# LDO.net
KiCad netlist of a schematic drawn in EAGLE
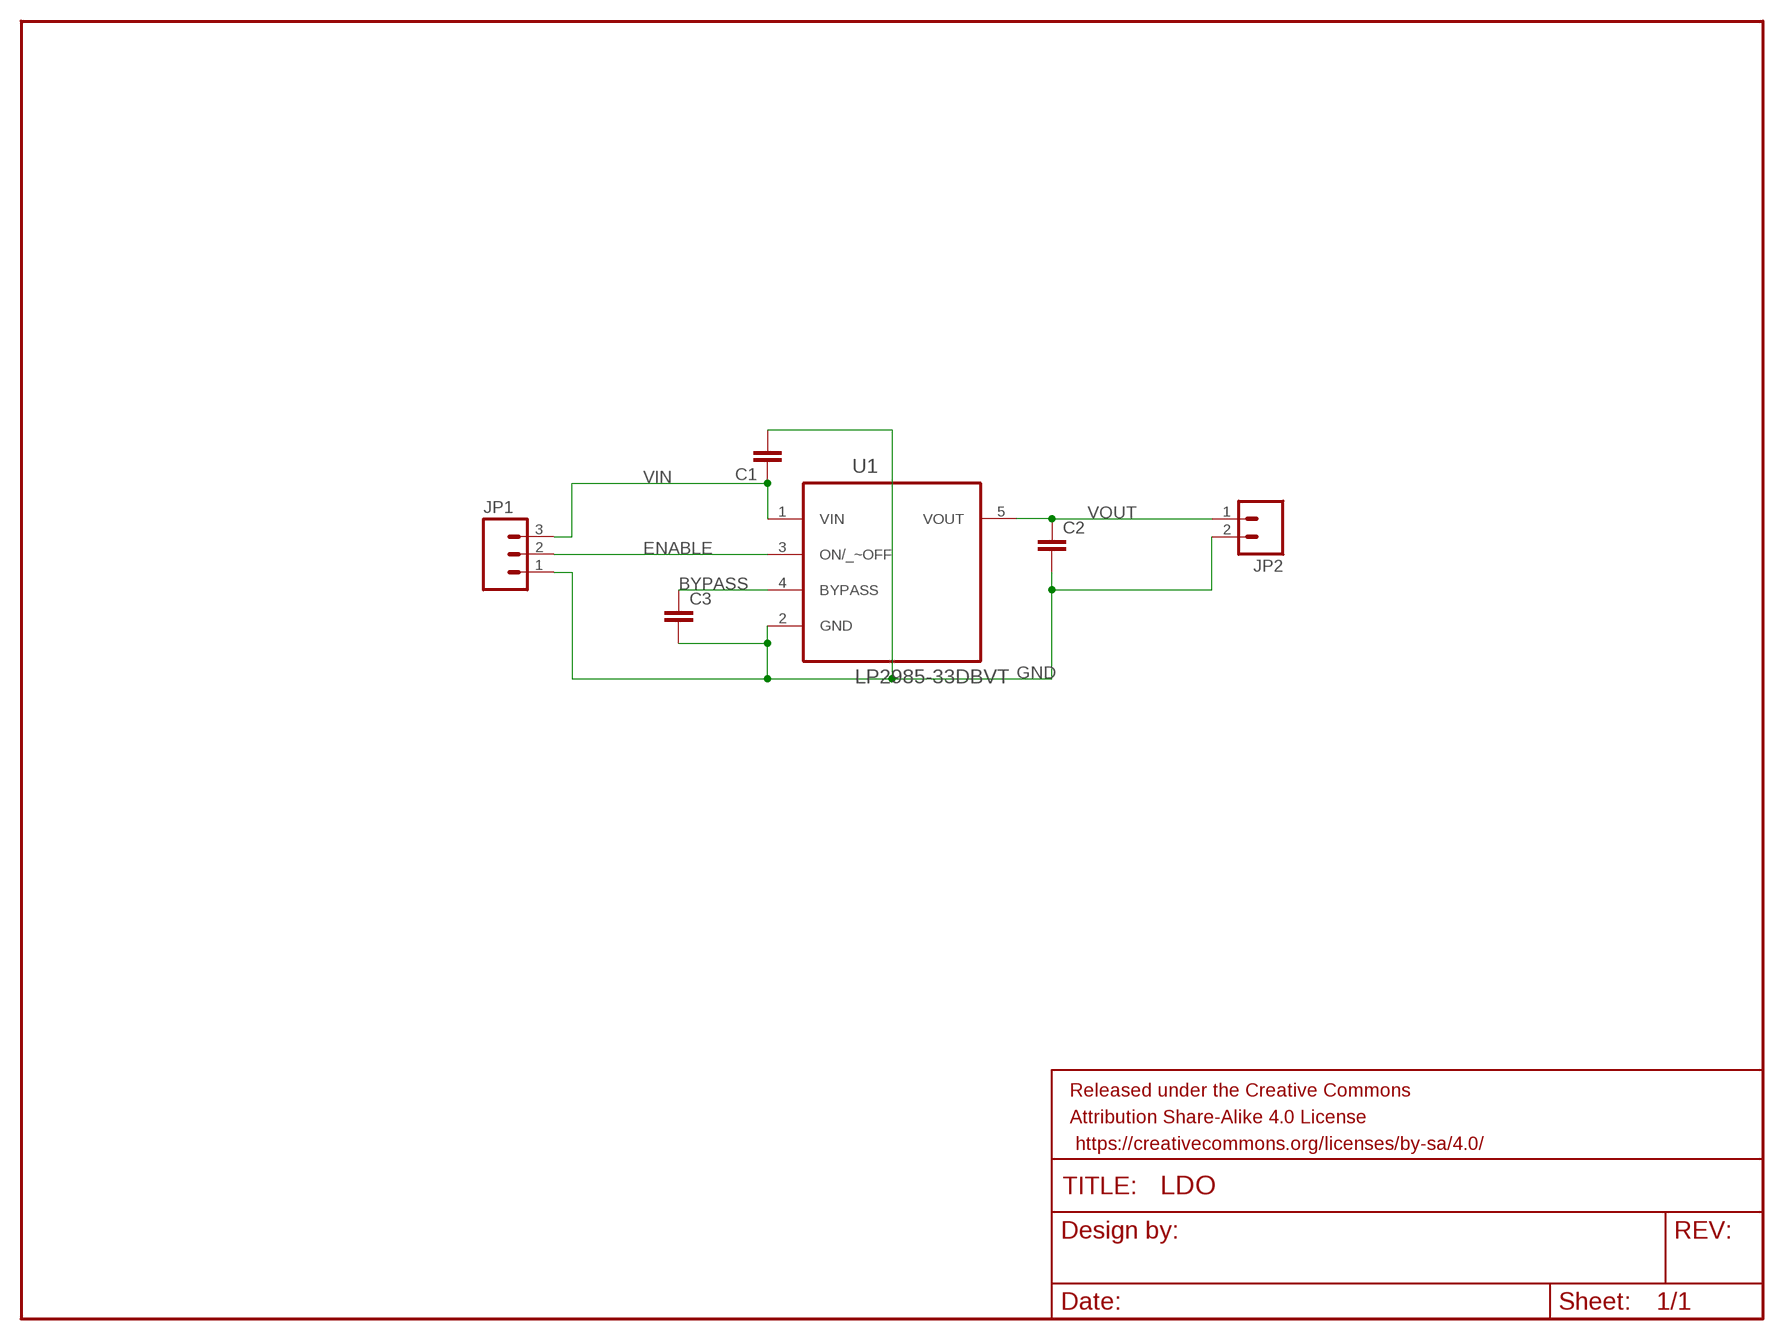
[diagram p0: schematic, sheet 1]

(export (version "E")
  (design (tool "Eeschema 10.0.6"))
  (components
    (comp (ref "C1")
      (value "CAP0603-CAP")
      (footprint "eagle-import:0603-CAP")
      (libsource (lib "eagle-import") (part "CAP0603-CAP"))
    )
    (comp (ref "C2")
      (value "CAP0603-CAP")
      (footprint "eagle-import:0603-CAP")
      (libsource (lib "eagle-import") (part "CAP0603-CAP"))
    )
    (comp (ref "C3")
      (value "CAP0603-CAP")
      (footprint "eagle-import:0603-CAP")
      (libsource (lib "eagle-import") (part "CAP0603-CAP"))
    )
    (comp (ref "FRAME1")
      (value "FRAME-LETTER")
      (footprint "eagle-import:CREATIVE_COMMONS")
      (libsource (lib "eagle-import") (part "FRAME-LETTER"))
    )
    (comp (ref "JP1")
      (value "M03PTH")
      (footprint "eagle-import:1X03")
      (libsource (lib "eagle-import") (part "M03PTH"))
    )
    (comp (ref "JP2")
      (value "M02PTH")
      (footprint "eagle-import:1X02")
      (libsource (lib "eagle-import") (part "M02PTH"))
    )
    (comp (ref "U1")
      (value "LP2985-33DBVT")
      (footprint "eagle-import:SOT95P280X145-5N")
      (fields (field (name "MF") "Texas Instruments"))
      (libsource (lib "eagle-import") (part "LP2985-33DBVT"))
    )
  )
  (nets
    (net (code "1") (name "/BYPASS") (class "Default")
      (node (ref "C3") (pin "1") (pinfunction "1_1") (pintype "passive"))
      (node (ref "U1") (pin "4") (pinfunction "BYPASS_4") (pintype "input"))
    )
    (net (code "2") (name "/ENABLE") (class "Default")
      (node (ref "JP1") (pin "2") (pinfunction "2_2") (pintype "passive"))
      (node (ref "U1") (pin "3") (pinfunction "ON/_~{OFF}_3") (pintype "input"))
    )
    (net (code "3") (name "/GND") (class "Default")
      (node (ref "C1") (pin "2") (pinfunction "2_2") (pintype "passive"))
      (node (ref "C2") (pin "2") (pinfunction "2_2") (pintype "passive"))
      (node (ref "C3") (pin "2") (pinfunction "2_2") (pintype "passive"))
      (node (ref "JP1") (pin "1") (pinfunction "1_1") (pintype "passive"))
      (node (ref "JP2") (pin "2") (pinfunction "2_2") (pintype "passive"))
      (node (ref "U1") (pin "2") (pinfunction "GND_2") (pintype "passive"))
    )
    (net (code "4") (name "/VIN") (class "Default")
      (node (ref "C1") (pin "1") (pinfunction "1_1") (pintype "passive"))
      (node (ref "JP1") (pin "3") (pinfunction "3_3") (pintype "passive"))
      (node (ref "U1") (pin "1") (pinfunction "VIN_1") (pintype "power_in"))
    )
    (net (code "5") (name "/VOUT") (class "Default")
      (node (ref "C2") (pin "1") (pinfunction "1_1") (pintype "passive"))
      (node (ref "JP2") (pin "1") (pinfunction "1_1") (pintype "passive"))
      (node (ref "U1") (pin "5") (pinfunction "VOUT_5") (pintype "output"))
    )
  )
)
